# 1-Schematic_EMWAVER_SMA.net
KiCad netlist of a schematic drawn in EasyEDA
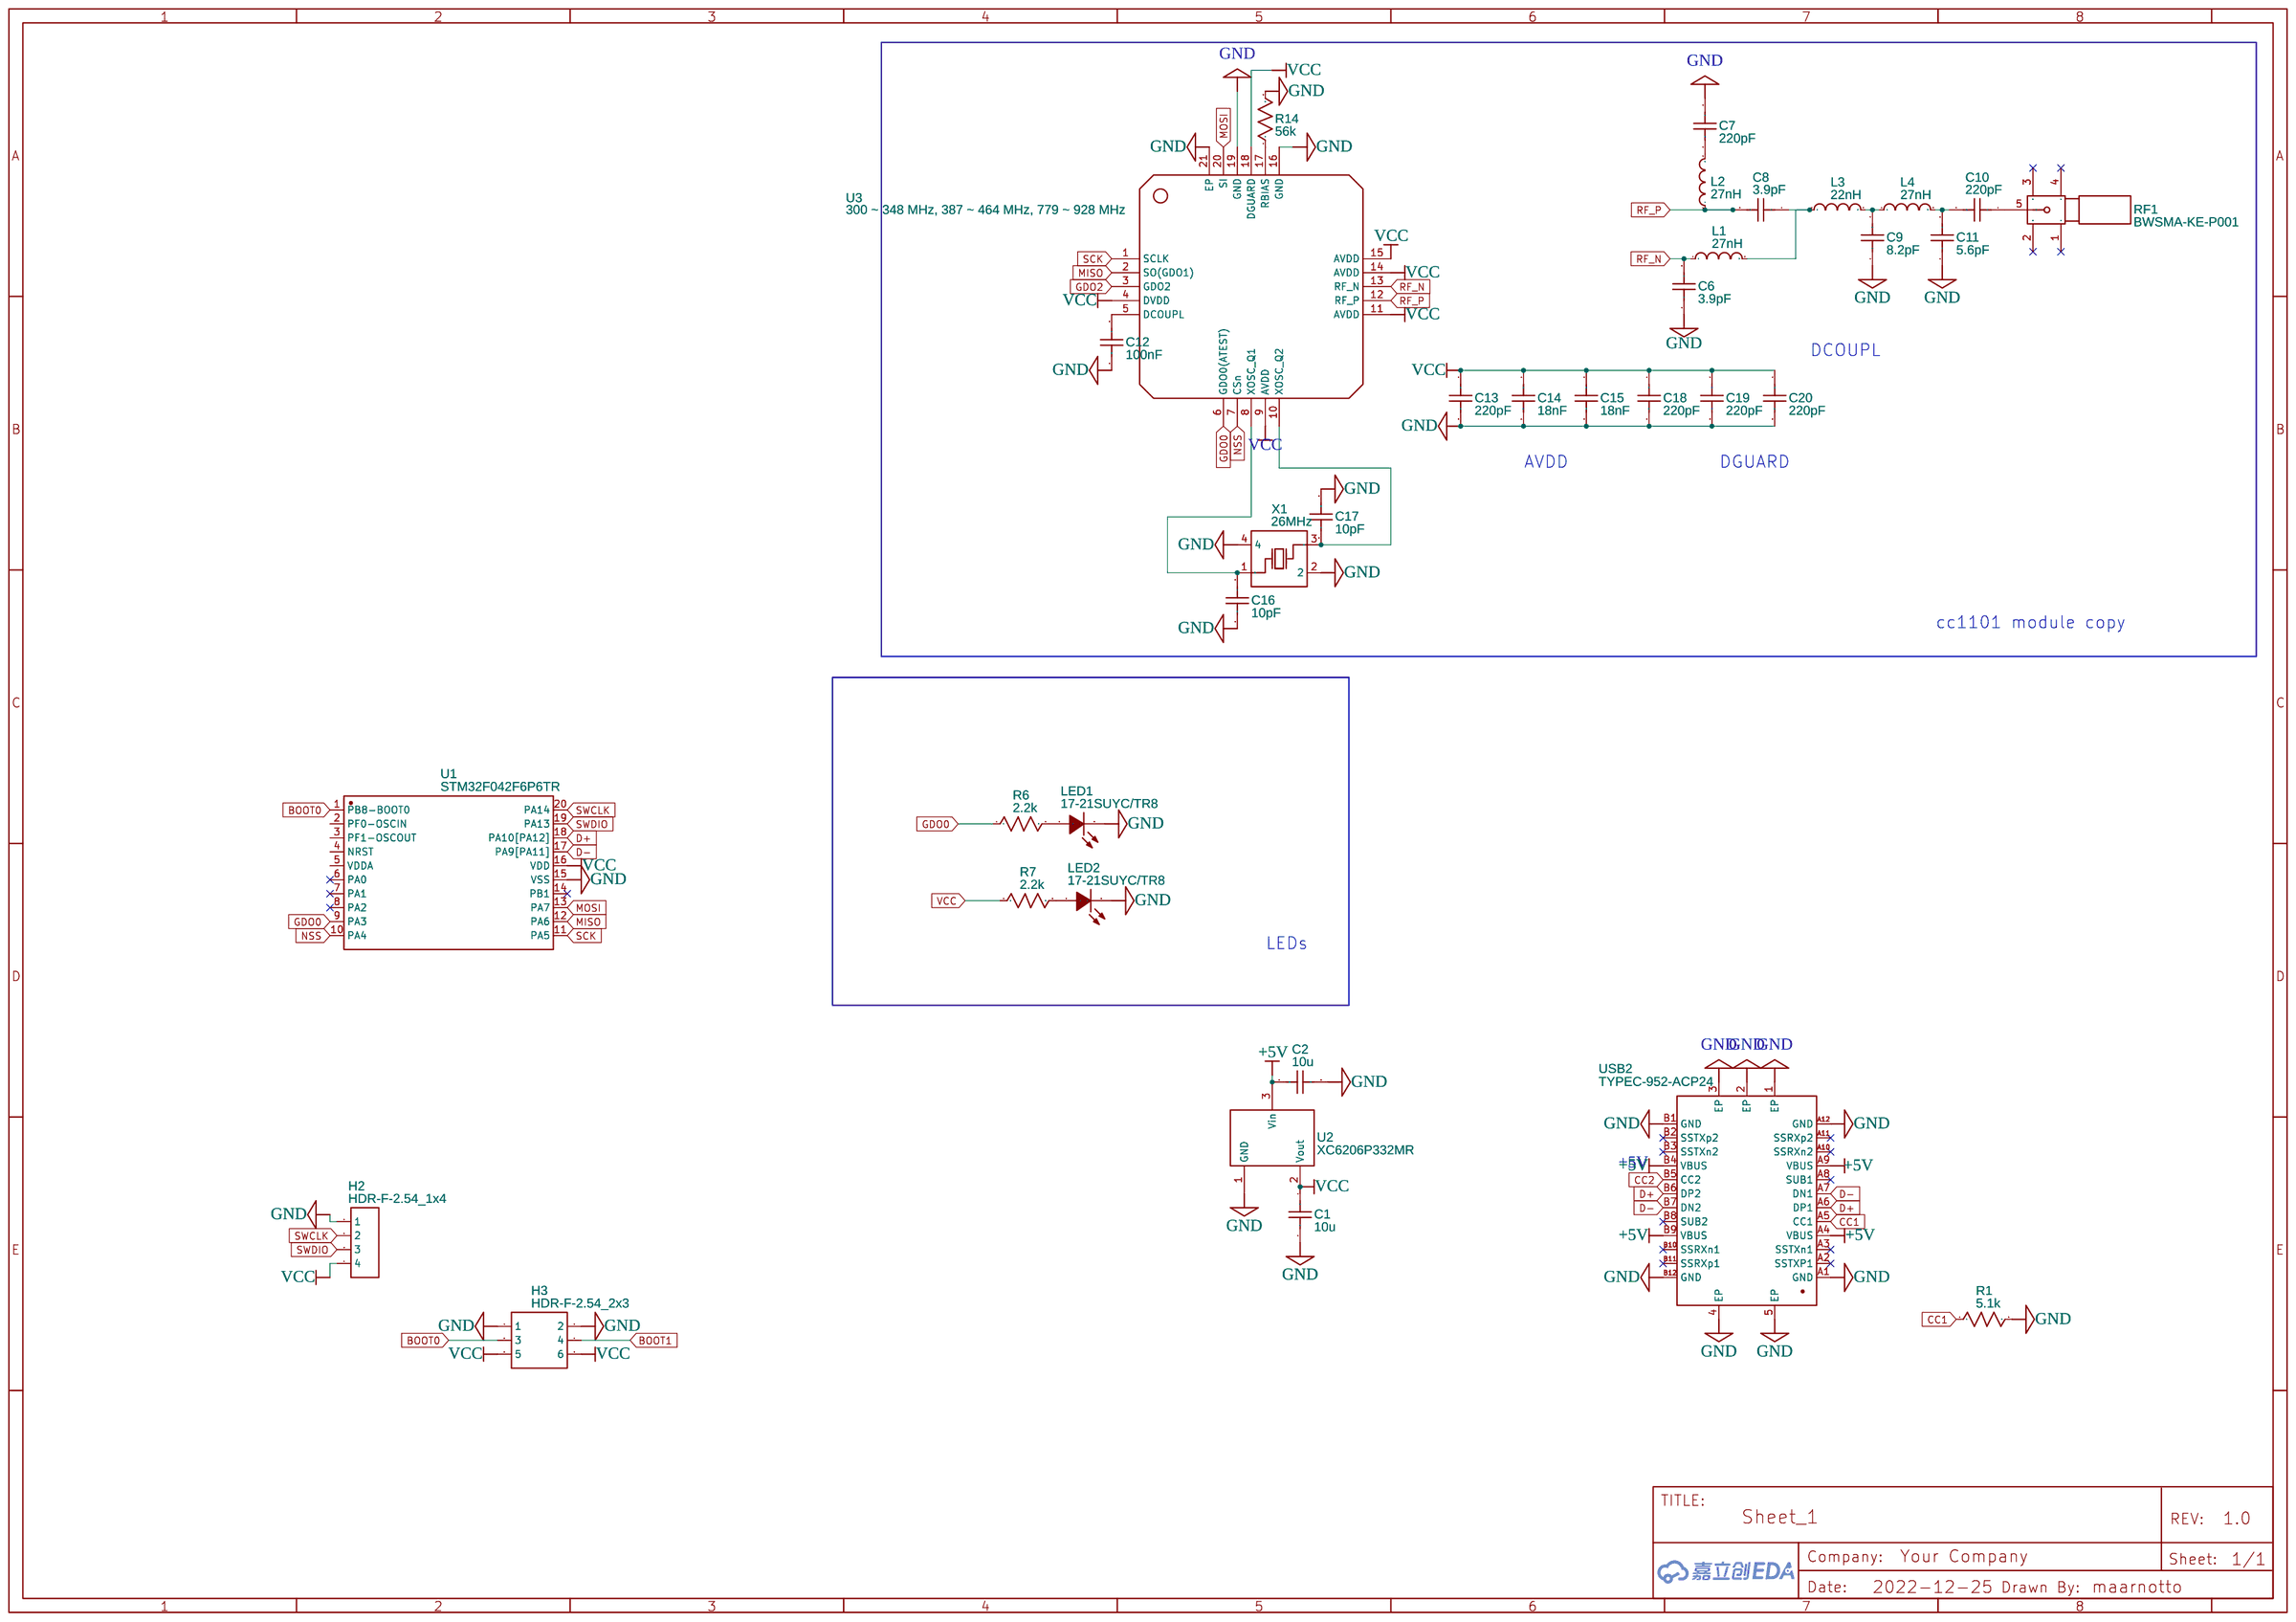
[diagram p0: schematic sheet]

(export (version "E")
  (design (tool "Eeschema 10.0.6"))
  (components
    (comp (ref "C1") (value "10u") (libsource (lib "") (part "C_0603_US")))
    (comp (ref "C2") (value "10u") (libsource (lib "") (part "C_0603_US_1")))
    (comp (ref "C6") (value "3.9pF") (libsource (lib "") (part "C_0402_US")))
    (comp (ref "C7") (value "220pF") (libsource (lib "") (part "C_0402_US")))
    (comp (ref "C8") (value "3.9pF") (libsource (lib "") (part "C_0402_US_1")))
    (comp (ref "C9") (value "8.2pF") (libsource (lib "") (part "C_0402_US")))
    (comp (ref "C10") (value "220pF") (libsource (lib "") (part "C_0402_US_1")))
    (comp (ref "C11") (value "5.6pF") (libsource (lib "") (part "C_0402_US")))
    (comp (ref "C12") (value "100nF") (libsource (lib "") (part "C_0402_US_2")))
    (comp (ref "C13") (value "220pF") (libsource (lib "") (part "C_0402_US_2")))
    (comp (ref "C14") (value "18nF") (libsource (lib "") (part "C_0402_US_2")))
    (comp (ref "C15") (value "18nF") (libsource (lib "") (part "C_0402_US_2")))
    (comp (ref "C16") (value "10pF") (libsource (lib "") (part "C_0402_US_2")))
    (comp (ref "C17") (value "10pF") (libsource (lib "") (part "C_0402_US")))
    (comp (ref "C18") (value "220pF") (libsource (lib "") (part "C_0402_US_2")))
    (comp (ref "C19") (value "220pF") (libsource (lib "") (part "C_0402_US_2")))
    (comp (ref "C20") (value "220pF") (libsource (lib "") (part "C_0402_US_2")))
    (comp (ref "H2")
      (value "HDR-F-2.54_1x4")
      (fields (field (name "BOM_Supplier Part") "C225501"))
      (libsource (lib "") (part "HDR-F-2.54_1x4"))
    )
    (comp (ref "H3")
      (value "HDR-F-2.54_2x3")
      (fields (field (name "BOM_Supplier Part") "C65114"))
      (libsource (lib "") (part "HDR-F-2.54_2x3"))
    )
    (comp (ref "L1") (value "27nH") (libsource (lib "") (part "L0402_US")))
    (comp (ref "L2") (value "27nH") (libsource (lib "") (part "L0402_US_1")))
    (comp (ref "L3") (value "22nH") (libsource (lib "") (part "L0402_US")))
    (comp (ref "L4") (value "27nH") (libsource (lib "") (part "L0402_US")))
    (comp (ref "LED1")
      (value "17-21SUYC/TR8")
      (fields
        (field (name "BOM_Manufacturer Part") "KT-0805黄灯 (SMT业务专用)")
        (field (name "BOM_Supplier Part") "C2296")
      )
      (libsource (lib "") (part "17-21SUYC/TR8"))
    )
    (comp (ref "LED2")
      (value "17-21SUYC/TR8")
      (fields
        (field (name "BOM_Manufacturer Part") "KT-0805黄灯 (SMT业务专用)")
        (field (name "BOM_Supplier Part") "C2296")
      )
      (libsource (lib "") (part "17-21SUYC/TR8"))
    )
    (comp (ref "R1") (value "5.1k") (libsource (lib "") (part "R_0603_US")))
    (comp (ref "R6") (value "2.2k") (libsource (lib "") (part "R_0603_US")))
    (comp (ref "R7") (value "2.2k") (libsource (lib "") (part "R_0603_US")))
    (comp (ref "R14") (value "56k") (libsource (lib "") (part "R_0402_US")))
    (comp (ref "RF1")
      (value "BWSMA-KE-P001")
      (fields (field (name "BOM_Supplier Part") "C496550"))
      (libsource (lib "") (part "BWSMA-KE-P001"))
    )
    (comp (ref "U1")
      (value "STM32F042F6P6TR")
      (fields (field (name "BOM_Supplier Part") "C2969989"))
      (libsource (lib "") (part "STM32F042F6P6TR"))
    )
    (comp (ref "U2")
      (value "XC6206P332MR")
      (fields (field (name "BOM_Supplier Part") "C5446"))
      (libsource (lib "") (part "XC6206P332MR"))
    )
    (comp (ref "U3")
      (value "300 ~ 348 MHz, 387 ~ 464 MHz, 779 ~ 928 MHz")
      (fields (field (name "BOM_Manufacturer Part") "CC1101RGPR") (field (name "BOM_Supplier Part") "C29953"))
      (libsource (lib "") (part "CC1101RGPR"))
    )
    (comp (ref "USB2")
      (value "TYPEC-952-ACP24")
      (fields (field (name "BOM_Supplier Part") "C2840398"))
      (libsource (lib "") (part "TYPEC-952-ACP24"))
    )
    (comp (ref "X1")
      (value "26MHz")
      (fields
        (field (name "BOM_Manufacturer Part") "3S26000333")
        (field (name "BOM_Supplier Part") "C431163")
      )
      (libsource (lib "") (part "3S26000333"))
    )
  )
  (nets
    (net (code "1") (name "+5V") (class "Default")
      (node (ref "C2") (pin "2") (pinfunction "2_2") (pintype "unspecified"))
      (node (ref "U2") (pin "3") (pinfunction "Vin_3") (pintype "unspecified"))
      (node (ref "USB2") (pin "A4") (pinfunction "VBUS_A4") (pintype "unspecified"))
      (node (ref "USB2") (pin "A9") (pinfunction "VBUS_A9") (pintype "unspecified"))
      (node (ref "USB2") (pin "B4") (pinfunction "VBUS_B4") (pintype "unspecified"))
      (node (ref "USB2") (pin "B9") (pinfunction "VBUS_B9") (pintype "unspecified"))
    )
    (net (code "2") (name "BOOT0") (class "Default")
      (node (ref "H3") (pin "3") (pinfunction "3_3") (pintype "input"))
      (node (ref "U1") (pin "1") (pinfunction "PB8-BOOT0_1") (pintype "unspecified"))
    )
    (net (code "3") (name "BOOT1") (class "Default")
      (node (ref "H3") (pin "4") (pinfunction "4_4") (pintype "input"))
    )
    (net (code "4") (name "CC1") (class "Default")
      (node (ref "R1") (pin "1") (pinfunction "1_1") (pintype "unspecified"))
      (node (ref "USB2") (pin "A5") (pinfunction "CC1_A5") (pintype "unspecified"))
    )
    (net (code "5") (name "CC2") (class "Default")
      (node (ref "USB2") (pin "B5") (pinfunction "CC2_B5") (pintype "unspecified"))
    )
    (net (code "6") (name "D+") (class "Default")
      (node (ref "U1") (pin "18") (pinfunction "PA10[PA12]_18") (pintype "unspecified"))
      (node (ref "USB2") (pin "A6") (pinfunction "DP1_A6") (pintype "unspecified"))
      (node (ref "USB2") (pin "B6") (pinfunction "DP2_B6") (pintype "unspecified"))
    )
    (net (code "7") (name "D-") (class "Default")
      (node (ref "U1") (pin "17") (pinfunction "PA9[PA11]_17") (pintype "unspecified"))
      (node (ref "USB2") (pin "A7") (pinfunction "DN1_A7") (pintype "unspecified"))
      (node (ref "USB2") (pin "B7") (pinfunction "DN2_B7") (pintype "unspecified"))
    )
    (net (code "8") (name "GDO0") (class "Default")
      (node (ref "R6") (pin "1") (pinfunction "1_1") (pintype "unspecified"))
      (node (ref "U1") (pin "9") (pinfunction "PA3_9") (pintype "unspecified"))
      (node (ref "U3") (pin "6") (pinfunction "GDO0(ATEST)_6") (pintype "unspecified"))
    )
    (net (code "9") (name "GDO2") (class "Default")
      (node (ref "U3") (pin "3") (pinfunction "GDO2_3") (pintype "unspecified"))
    )
    (net (code "10") (name "GND") (class "Default")
      (node (ref "C1") (pin "2") (pinfunction "2_2") (pintype "unspecified"))
      (node (ref "C11") (pin "1") (pinfunction "1_1") (pintype "unspecified"))
      (node (ref "C12") (pin "2") (pinfunction "2_2") (pintype "unspecified"))
      (node (ref "C13") (pin "2") (pinfunction "2_2") (pintype "unspecified"))
      (node (ref "C14") (pin "2") (pinfunction "2_2") (pintype "unspecified"))
      (node (ref "C15") (pin "2") (pinfunction "2_2") (pintype "unspecified"))
      (node (ref "C16") (pin "2") (pinfunction "2_2") (pintype "unspecified"))
      (node (ref "C17") (pin "2") (pinfunction "2_2") (pintype "unspecified"))
      (node (ref "C18") (pin "2") (pinfunction "2_2") (pintype "unspecified"))
      (node (ref "C19") (pin "2") (pinfunction "2_2") (pintype "unspecified"))
      (node (ref "C2") (pin "1") (pinfunction "1_1") (pintype "unspecified"))
      (node (ref "C20") (pin "2") (pinfunction "2_2") (pintype "unspecified"))
      (node (ref "C6") (pin "1") (pinfunction "1_1") (pintype "unspecified"))
      (node (ref "C7") (pin "2") (pinfunction "2_2") (pintype "unspecified"))
      (node (ref "C9") (pin "1") (pinfunction "1_1") (pintype "unspecified"))
      (node (ref "H2") (pin "1") (pinfunction "1_1") (pintype "unspecified"))
      (node (ref "H3") (pin "1") (pinfunction "1_1") (pintype "input"))
      (node (ref "H3") (pin "2") (pinfunction "2_2") (pintype "input"))
      (node (ref "LED1") (pin "2") (pinfunction "-_2") (pintype "unspecified"))
      (node (ref "LED2") (pin "2") (pinfunction "-_2") (pintype "unspecified"))
      (node (ref "R1") (pin "2") (pinfunction "2_2") (pintype "unspecified"))
      (node (ref "R14") (pin "2") (pinfunction "2_2") (pintype "unspecified"))
      (node (ref "U1") (pin "15") (pinfunction "VSS_15") (pintype "unspecified"))
      (node (ref "U2") (pin "1") (pinfunction "GND_1") (pintype "unspecified"))
      (node (ref "U3") (pin "16") (pinfunction "GND_16") (pintype "unspecified"))
      (node (ref "U3") (pin "19") (pinfunction "GND_19") (pintype "unspecified"))
      (node (ref "U3") (pin "21") (pinfunction "EP_21") (pintype "unspecified"))
      (node (ref "USB2") (pin "1") (pinfunction "EP_1") (pintype "unspecified"))
      (node (ref "USB2") (pin "2") (pinfunction "EP_2") (pintype "unspecified"))
      (node (ref "USB2") (pin "3") (pinfunction "EP_3") (pintype "unspecified"))
      (node (ref "USB2") (pin "4") (pinfunction "EP_4") (pintype "unspecified"))
      (node (ref "USB2") (pin "5") (pinfunction "EP_5") (pintype "unspecified"))
      (node (ref "USB2") (pin "A1") (pinfunction "GND_A1") (pintype "unspecified"))
      (node (ref "USB2") (pin "A12") (pinfunction "GND_A12") (pintype "unspecified"))
      (node (ref "USB2") (pin "B1") (pinfunction "GND_B1") (pintype "unspecified"))
      (node (ref "USB2") (pin "B12") (pinfunction "GND_B12") (pintype "unspecified"))
      (node (ref "X1") (pin "2") (pinfunction "2_2") (pintype "unspecified"))
      (node (ref "X1") (pin "4") (pinfunction "4_4") (pintype "unspecified"))
    )
    (net (code "11") (name "MISO") (class "Default")
      (node (ref "U1") (pin "12") (pinfunction "PA6_12") (pintype "unspecified"))
      (node (ref "U3") (pin "2") (pinfunction "SO(GDO1)_2") (pintype "unspecified"))
    )
    (net (code "12") (name "MOSI") (class "Default")
      (node (ref "U1") (pin "13") (pinfunction "PA7_13") (pintype "unspecified"))
      (node (ref "U3") (pin "20") (pinfunction "SI_20") (pintype "unspecified"))
    )
    (net (code "13") (name "NSS") (class "Default")
      (node (ref "U1") (pin "10") (pinfunction "PA4_10") (pintype "unspecified"))
      (node (ref "U3") (pin "7") (pinfunction "CSn_7") (pintype "unspecified"))
    )
    (net (code "14") (name "Net-(C7-Pad1)") (class "Default")
      (node (ref "C7") (pin "1") (pinfunction "1_1") (pintype "unspecified"))
      (node (ref "L2") (pin "2") (pinfunction "2_2") (pintype "unspecified"))
    )
    (net (code "15") (name "Net-(C8-Pad1)") (class "Default")
      (node (ref "C8") (pin "1") (pinfunction "1_1") (pintype "unspecified"))
      (node (ref "L1") (pin "2") (pinfunction "2_2") (pintype "unspecified"))
      (node (ref "L3") (pin "1") (pinfunction "1_1") (pintype "unspecified"))
    )
    (net (code "16") (name "Net-(C9-Pad2)") (class "Default")
      (node (ref "C9") (pin "2") (pinfunction "2_2") (pintype "unspecified"))
      (node (ref "L3") (pin "2") (pinfunction "2_2") (pintype "unspecified"))
      (node (ref "L4") (pin "1") (pinfunction "1_1") (pintype "unspecified"))
    )
    (net (code "17") (name "Net-(C10-Pad1)") (class "Default")
      (node (ref "C10") (pin "1") (pinfunction "1_1") (pintype "unspecified"))
      (node (ref "RF1") (pin "5") (pinfunction "5_5") (pintype "unspecified"))
    )
    (net (code "18") (name "Net-(C10-Pad2)") (class "Default")
      (node (ref "C10") (pin "2") (pinfunction "2_2") (pintype "unspecified"))
      (node (ref "C11") (pin "2") (pinfunction "2_2") (pintype "unspecified"))
      (node (ref "L4") (pin "2") (pinfunction "2_2") (pintype "unspecified"))
    )
    (net (code "19") (name "Net-(LED1-+)") (class "Default")
      (node (ref "LED1") (pin "1") (pinfunction "+_1") (pintype "unspecified"))
      (node (ref "R6") (pin "2") (pinfunction "2_2") (pintype "unspecified"))
    )
    (net (code "20") (name "Net-(LED2-+)") (class "Default")
      (node (ref "LED2") (pin "1") (pinfunction "+_1") (pintype "unspecified"))
      (node (ref "R7") (pin "2") (pinfunction "2_2") (pintype "unspecified"))
    )
    (net (code "21") (name "Net-(U3-DCOUPL)") (class "Default")
      (node (ref "C12") (pin "1") (pinfunction "1_1") (pintype "unspecified"))
      (node (ref "U3") (pin "5") (pinfunction "DCOUPL_5") (pintype "unspecified"))
    )
    (net (code "22") (name "Net-(U3-RBIAS)") (class "Default")
      (node (ref "R14") (pin "1") (pinfunction "1_1") (pintype "unspecified"))
      (node (ref "U3") (pin "17") (pinfunction "RBIAS_17") (pintype "unspecified"))
    )
    (net (code "23") (name "Net-(U3-XOSC_Q1)") (class "Default")
      (node (ref "C16") (pin "1") (pinfunction "1_1") (pintype "unspecified"))
      (node (ref "U3") (pin "8") (pinfunction "XOSC_Q1_8") (pintype "unspecified"))
      (node (ref "X1") (pin "1") (pinfunction "OSC1_1") (pintype "unspecified"))
    )
    (net (code "24") (name "Net-(U3-XOSC_Q2)") (class "Default")
      (node (ref "C17") (pin "1") (pinfunction "1_1") (pintype "unspecified"))
      (node (ref "U3") (pin "10") (pinfunction "XOSC_Q2_10") (pintype "unspecified"))
      (node (ref "X1") (pin "3") (pinfunction "OSC2_3") (pintype "unspecified"))
    )
    (net (code "25") (name "RF_N") (class "Default")
      (node (ref "C6") (pin "2") (pinfunction "2_2") (pintype "unspecified"))
      (node (ref "L1") (pin "1") (pinfunction "1_1") (pintype "unspecified"))
      (node (ref "U3") (pin "13") (pinfunction "RF_N_13") (pintype "unspecified"))
    )
    (net (code "26") (name "RF_P") (class "Default")
      (node (ref "C8") (pin "2") (pinfunction "2_2") (pintype "unspecified"))
      (node (ref "L2") (pin "1") (pinfunction "1_1") (pintype "unspecified"))
      (node (ref "U3") (pin "12") (pinfunction "RF_P_12") (pintype "unspecified"))
    )
    (net (code "27") (name "SCK") (class "Default")
      (node (ref "U1") (pin "11") (pinfunction "PA5_11") (pintype "unspecified"))
      (node (ref "U3") (pin "1") (pinfunction "SCLK_1") (pintype "unspecified"))
    )
    (net (code "28") (name "SWCLK") (class "Default")
      (node (ref "H2") (pin "2") (pinfunction "2_2") (pintype "unspecified"))
      (node (ref "U1") (pin "20") (pinfunction "PA14_20") (pintype "unspecified"))
    )
    (net (code "29") (name "SWDIO") (class "Default")
      (node (ref "H2") (pin "3") (pinfunction "3_3") (pintype "unspecified"))
      (node (ref "U1") (pin "19") (pinfunction "PA13_19") (pintype "unspecified"))
    )
    (net (code "30") (name "VCC") (class "Default")
      (node (ref "C1") (pin "1") (pinfunction "1_1") (pintype "unspecified"))
      (node (ref "C13") (pin "1") (pinfunction "1_1") (pintype "unspecified"))
      (node (ref "C14") (pin "1") (pinfunction "1_1") (pintype "unspecified"))
      (node (ref "C15") (pin "1") (pinfunction "1_1") (pintype "unspecified"))
      (node (ref "C18") (pin "1") (pinfunction "1_1") (pintype "unspecified"))
      (node (ref "C19") (pin "1") (pinfunction "1_1") (pintype "unspecified"))
      (node (ref "C20") (pin "1") (pinfunction "1_1") (pintype "unspecified"))
      (node (ref "H2") (pin "4") (pinfunction "4_4") (pintype "unspecified"))
      (node (ref "H3") (pin "5") (pinfunction "5_5") (pintype "input"))
      (node (ref "H3") (pin "6") (pinfunction "6_6") (pintype "input"))
      (node (ref "R7") (pin "1") (pinfunction "1_1") (pintype "unspecified"))
      (node (ref "U1") (pin "16") (pinfunction "VDD_16") (pintype "unspecified"))
      (node (ref "U2") (pin "2") (pinfunction "Vout_2") (pintype "unspecified"))
      (node (ref "U3") (pin "11") (pinfunction "AVDD_11") (pintype "unspecified"))
      (node (ref "U3") (pin "14") (pinfunction "AVDD_14") (pintype "unspecified"))
      (node (ref "U3") (pin "15") (pinfunction "AVDD_15") (pintype "unspecified"))
      (node (ref "U3") (pin "18") (pinfunction "DGUARD_18") (pintype "unspecified"))
      (node (ref "U3") (pin "4") (pinfunction "DVDD_4") (pintype "unspecified"))
      (node (ref "U3") (pin "9") (pinfunction "AVDD_9") (pintype "unspecified"))
    )
    (net (code "31") (name "unconnected-(RF1-Pad1)") (class "Default")
      (node (ref "RF1") (pin "1") (pinfunction "1_1") (pintype "unspecified+no_connect"))
    )
    (net (code "32") (name "unconnected-(RF1-Pad2)") (class "Default")
      (node (ref "RF1") (pin "2") (pinfunction "2_2") (pintype "unspecified+no_connect"))
    )
    (net (code "33") (name "unconnected-(RF1-Pad3)") (class "Default")
      (node (ref "RF1") (pin "3") (pinfunction "3_3") (pintype "unspecified+no_connect"))
    )
    (net (code "34") (name "unconnected-(RF1-Pad4)") (class "Default")
      (node (ref "RF1") (pin "4") (pinfunction "4_4") (pintype "unspecified+no_connect"))
    )
    (net (code "35") (name "unconnected-(U1-NRST-Pad4)") (class "Default")
      (node (ref "U1") (pin "4") (pinfunction "NRST_4") (pintype "unspecified"))
    )
    (net (code "36") (name "unconnected-(U1-PA0-Pad6)") (class "Default")
      (node (ref "U1") (pin "6") (pinfunction "PA0_6") (pintype "unspecified+no_connect"))
    )
    (net (code "37") (name "unconnected-(U1-PA1-Pad7)") (class "Default")
      (node (ref "U1") (pin "7") (pinfunction "PA1_7") (pintype "unspecified+no_connect"))
    )
    (net (code "38") (name "unconnected-(U1-PA2-Pad8)") (class "Default")
      (node (ref "U1") (pin "8") (pinfunction "PA2_8") (pintype "unspecified+no_connect"))
    )
    (net (code "39") (name "unconnected-(U1-PB1-Pad14)") (class "Default")
      (node (ref "U1") (pin "14") (pinfunction "PB1_14") (pintype "unspecified+no_connect"))
    )
    (net (code "40") (name "unconnected-(U1-PF0-OSCIN-Pad2)") (class "Default")
      (node (ref "U1") (pin "2") (pinfunction "PF0-OSCIN_2") (pintype "unspecified"))
    )
    (net (code "41") (name "unconnected-(U1-PF1-OSCOUT-Pad3)") (class "Default")
      (node (ref "U1") (pin "3") (pinfunction "PF1-OSCOUT_3") (pintype "unspecified"))
    )
    (net (code "42") (name "unconnected-(U1-VDDA-Pad5)") (class "Default")
      (node (ref "U1") (pin "5") (pinfunction "VDDA_5") (pintype "unspecified"))
    )
    (net (code "43") (name "unconnected-(USB2-SSRXn1-PadB10)") (class "Default")
      (node (ref "USB2") (pin "B10") (pinfunction "SSRXn1_B10") (pintype "unspecified+no_connect"))
    )
    (net (code "44") (name "unconnected-(USB2-SSRXn2-PadA10)") (class "Default")
      (node (ref "USB2") (pin "A10") (pinfunction "SSRXn2_A10") (pintype "unspecified+no_connect"))
    )
    (net (code "45") (name "unconnected-(USB2-SSRXp1-PadB11)") (class "Default")
      (node (ref "USB2") (pin "B11") (pinfunction "SSRXp1_B11") (pintype "unspecified+no_connect"))
    )
    (net (code "46") (name "unconnected-(USB2-SSRXp2-PadA11)") (class "Default")
      (node (ref "USB2") (pin "A11") (pinfunction "SSRXp2_A11") (pintype "unspecified+no_connect"))
    )
    (net (code "47") (name "unconnected-(USB2-SSTXP1-PadA2)") (class "Default")
      (node (ref "USB2") (pin "A2") (pinfunction "SSTXP1_A2") (pintype "unspecified+no_connect"))
    )
    (net (code "48") (name "unconnected-(USB2-SSTXn1-PadA3)") (class "Default")
      (node (ref "USB2") (pin "A3") (pinfunction "SSTXn1_A3") (pintype "unspecified+no_connect"))
    )
    (net (code "49") (name "unconnected-(USB2-SSTXn2-PadB3)") (class "Default")
      (node (ref "USB2") (pin "B3") (pinfunction "SSTXn2_B3") (pintype "unspecified+no_connect"))
    )
    (net (code "50") (name "unconnected-(USB2-SSTXp2-PadB2)") (class "Default")
      (node (ref "USB2") (pin "B2") (pinfunction "SSTXp2_B2") (pintype "unspecified+no_connect"))
    )
    (net (code "51") (name "unconnected-(USB2-SUB1-PadA8)") (class "Default")
      (node (ref "USB2") (pin "A8") (pinfunction "SUB1_A8") (pintype "unspecified+no_connect"))
    )
    (net (code "52") (name "unconnected-(USB2-SUB2-PadB8)") (class "Default")
      (node (ref "USB2") (pin "B8") (pinfunction "SUB2_B8") (pintype "unspecified+no_connect"))
    )
  )
)
